# Memory.net
KiCad netlist of a schematic drawn in Altium Designer
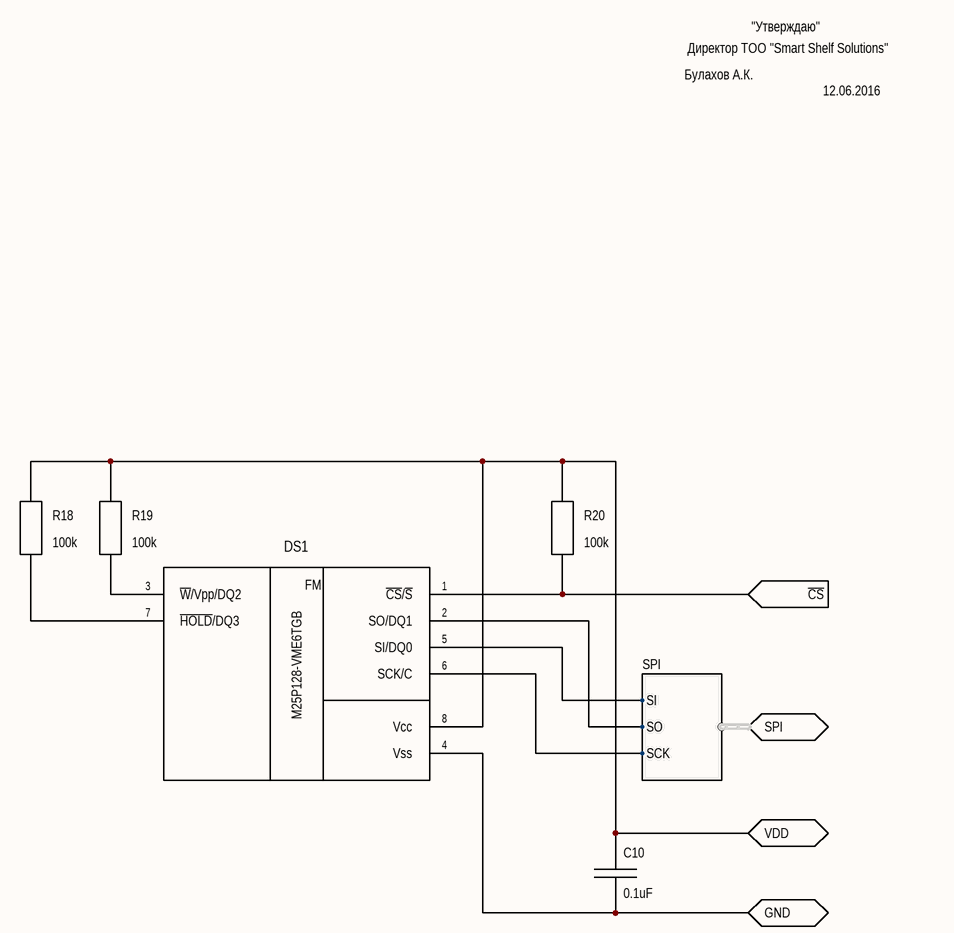
[diagram p0: Memory.SchDoc]

(export (version "E")
  (design (tool "Eeschema 10.0.6"))
  (components
    (comp (ref "C10")
      (value "0.1uF")
      (footprint "CAPC1608L")
      (description "Capacitor Ceramic 0.1uF 25V")
      (fields (field (name "TOLERANCE") "±10%") (field (name "MANUFACTURER") "Yageo"))
      (libsource (lib "Capacitors") (part "CC0603KRX7R8BB104"))
    )
    (comp (ref "DS1")
      (value "M25P128-VME6TGB")
      (footprint "VDFPN-8 (8x6)")
      (description "Memory Flash 128M (16M x 8)")
      (fields (field (name "MANUFACTURER") "Micron Technology"))
      (libsource (lib "ICs") (part "M25P128-VME6TGB"))
    )
    (comp (ref "R18")
      (value "100k")
      (footprint "RESC1608L")
      (description "Resistor Ceramic 100k 1608")
      (fields (field (name "MANUFACTURER") "Yageo") (field (name "TOLERANCE") "±5%"))
      (libsource (lib "Resistors") (part "RC0603JR-10100KL"))
    )
    (comp (ref "R19")
      (value "100k")
      (footprint "RESC1608L")
      (description "Resistor Ceramic 100k 1608")
      (fields (field (name "MANUFACTURER") "Yageo") (field (name "TOLERANCE") "±5%"))
      (libsource (lib "Resistors") (part "RC0603JR-10100KL"))
    )
    (comp (ref "R20")
      (value "100k")
      (footprint "RESC1608L")
      (description "Resistor Ceramic 100k 1608")
      (fields (field (name "MANUFACTURER") "Yageo") (field (name "TOLERANCE") "±5%"))
      (libsource (lib "Resistors") (part "RC0603JR-10100KL"))
    )
  )
  (nets
    (net (code "2") (name "/GND") (class "Default")
      (node (ref "C10") (pin "2") (pinfunction "2_2") (pintype "passive"))
      (node (ref "DS1") (pin "4") (pinfunction "Vss_4") (pintype "passive"))
    )
    (net (code "3") (name "/SCK") (class "Default")
      (node (ref "DS1") (pin "6") (pinfunction "SCK/C_6") (pintype "passive"))
    )
    (net (code "4") (name "/SI") (class "Default")
      (node (ref "DS1") (pin "5") (pinfunction "SI/DQ0_5") (pintype "passive"))
    )
    (net (code "5") (name "/SO") (class "Default")
      (node (ref "DS1") (pin "2") (pinfunction "SO/DQ1_2") (pintype "passive"))
    )
    (net (code "6") (name "/VDD") (class "Default")
      (node (ref "C10") (pin "1") (pinfunction "1_1") (pintype "passive"))
      (node (ref "DS1") (pin "8") (pinfunction "Vcc_8") (pintype "passive"))
      (node (ref "R18") (pin "1") (pinfunction "1_1") (pintype "passive"))
      (node (ref "R19") (pin "1") (pinfunction "1_1") (pintype "passive"))
      (node (ref "R20") (pin "1") (pinfunction "1_1") (pintype "passive"))
    )
    (net (code "8") (name "/~{CS}") (class "Default")
      (node (ref "DS1") (pin "1") (pinfunction "~{CS}/~{S}_1") (pintype "passive"))
      (node (ref "R20") (pin "2") (pinfunction "2_2") (pintype "passive"))
    )
    (net (code "9") (name "Net-(DS1-~{HOLD}{slash}DQ3)") (class "Default")
      (node (ref "DS1") (pin "7") (pinfunction "~{HOLD}/DQ3_7") (pintype "passive"))
      (node (ref "R18") (pin "2") (pinfunction "2_2") (pintype "passive"))
    )
    (net (code "10") (name "Net-(DS1-~{W}{slash}Vpp{slash}DQ2)") (class "Default")
      (node (ref "DS1") (pin "3") (pinfunction "~{W}/Vpp/DQ2_3") (pintype "passive"))
      (node (ref "R19") (pin "2") (pinfunction "2_2") (pintype "passive"))
    )
  )
)
